# PF11_DigiPot_Cutoff.net
KiCad netlist of a schematic drawn in Altium Designer
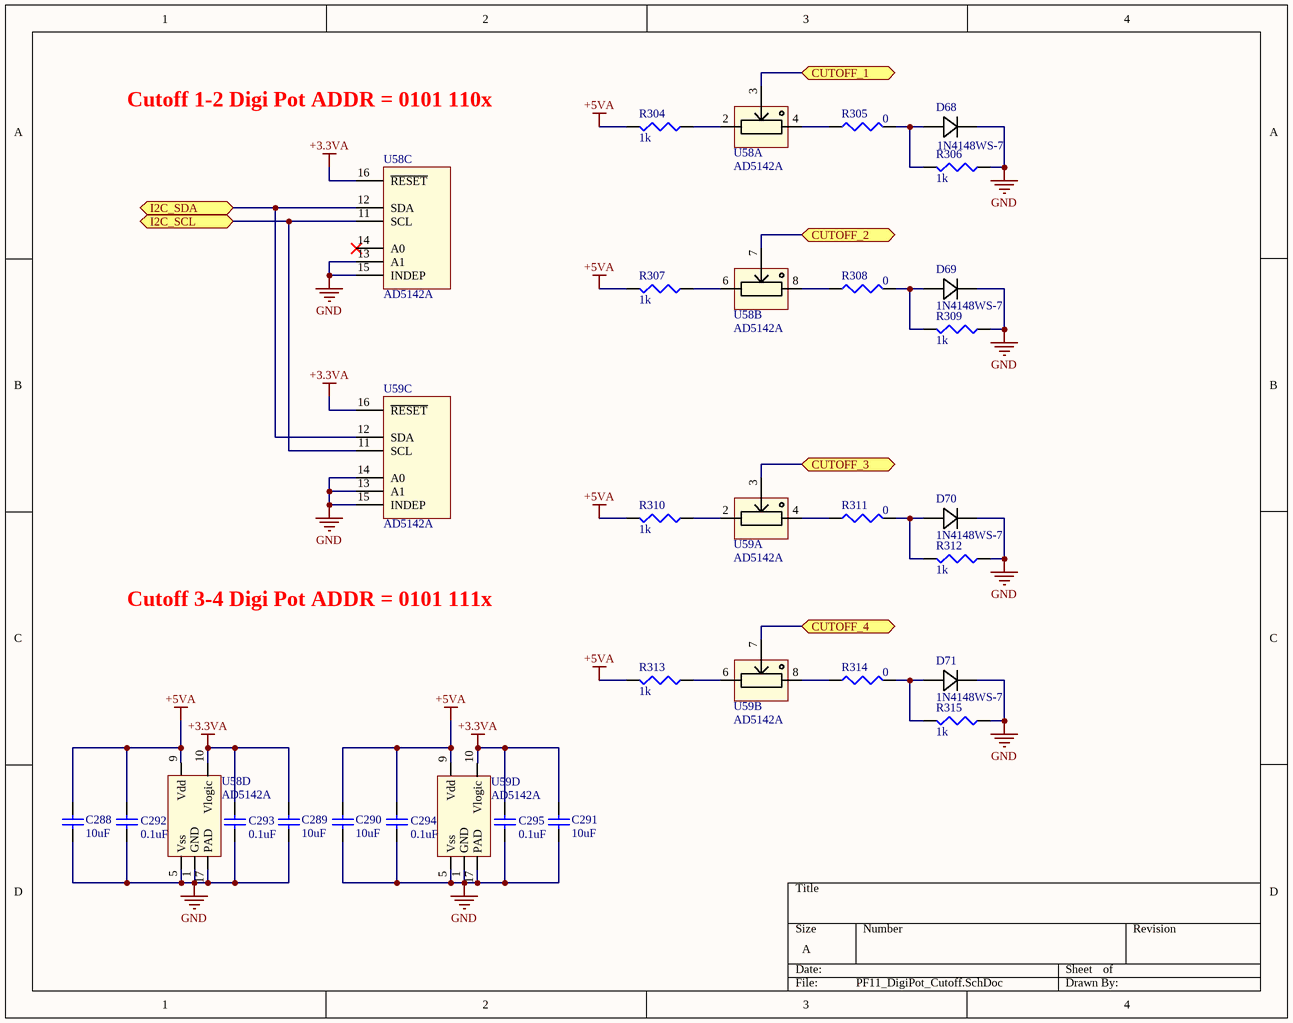
[diagram p0: PF11_DigiPot_Cutoff.SchDoc]

(export (version "E")
  (design (tool "Eeschema 10.0.6"))
  (components
    (comp (ref "C288")
      (value "10uF")
      (footprint "CAPC1608X08")
      (description "Capacitor (Semiconductor SIM Model)")
      (libsource (lib "Michel") (part "Cap Semi"))
    )
    (comp (ref "C289")
      (value "10uF")
      (footprint "CAPC1608X08")
      (description "Capacitor (Semiconductor SIM Model)")
      (libsource (lib "Michel") (part "Cap Semi"))
    )
    (comp (ref "C290")
      (value "10uF")
      (footprint "CAPC1608X08")
      (description "Capacitor (Semiconductor SIM Model)")
      (libsource (lib "Michel") (part "Cap Semi"))
    )
    (comp (ref "C291")
      (value "10uF")
      (footprint "CAPC1608X08")
      (description "Capacitor (Semiconductor SIM Model)")
      (libsource (lib "Michel") (part "Cap Semi"))
    )
    (comp (ref "C292")
      (value "0.1uF")
      (footprint "CAPC1608X08")
      (description "Capacitor (Semiconductor SIM Model)")
      (libsource (lib "Michel") (part "Cap Semi"))
    )
    (comp (ref "C293")
      (value "0.1uF")
      (footprint "CAPC1608X08")
      (description "Capacitor (Semiconductor SIM Model)")
      (libsource (lib "Michel") (part "Cap Semi"))
    )
    (comp (ref "C294")
      (value "0.1uF")
      (footprint "CAPC1608X08")
      (description "Capacitor (Semiconductor SIM Model)")
      (libsource (lib "Michel") (part "Cap Semi"))
    )
    (comp (ref "C295")
      (value "0.1uF")
      (footprint "CAPC1608X08")
      (description "Capacitor (Semiconductor SIM Model)")
      (libsource (lib "Michel") (part "Cap Semi"))
    )
    (comp (ref "D68")
      (value "1N4148WS-7")
      (footprint "SOD323-M")
      (description "Diode signaux faibles")
      (libsource (lib "Michel") (part "1N4148WS-7"))
    )
    (comp (ref "D69")
      (value "1N4148WS-7")
      (footprint "SOD323-M")
      (description "Diode signaux faibles")
      (libsource (lib "Michel") (part "1N4148WS-7"))
    )
    (comp (ref "D70")
      (value "1N4148WS-7")
      (footprint "SOD323-M")
      (description "Diode signaux faibles")
      (libsource (lib "Michel") (part "1N4148WS-7"))
    )
    (comp (ref "D71")
      (value "1N4148WS-7")
      (footprint "SOD323-M")
      (description "Diode signaux faibles")
      (libsource (lib "Michel") (part "1N4148WS-7"))
    )
    (comp (ref "R304")
      (value "1k")
      (footprint "RESC1608X05")
      (description "Resistor")
      (libsource (lib "Michel") (part "Res3"))
    )
    (comp (ref "R305")
      (value "0")
      (footprint "RESC1608X05")
      (description "Resistor")
      (fields (field (name "Comment") "Res3"))
      (libsource (lib "Michel") (part "Res3"))
    )
    (comp (ref "R306")
      (value "1k")
      (footprint "RESC1608X05")
      (description "Resistor")
      (libsource (lib "Michel") (part "Res3"))
    )
    (comp (ref "R307")
      (value "1k")
      (footprint "RESC1608X05")
      (description "Resistor")
      (libsource (lib "Michel") (part "Res3"))
    )
    (comp (ref "R308")
      (value "0")
      (footprint "RESC1608X05")
      (description "Resistor")
      (fields (field (name "Comment") "Res3"))
      (libsource (lib "Michel") (part "Res3"))
    )
    (comp (ref "R309")
      (value "1k")
      (footprint "RESC1608X05")
      (description "Resistor")
      (libsource (lib "Michel") (part "Res3"))
    )
    (comp (ref "R310")
      (value "1k")
      (footprint "RESC1608X05")
      (description "Resistor")
      (libsource (lib "Michel") (part "Res3"))
    )
    (comp (ref "R311")
      (value "0")
      (footprint "RESC1608X05")
      (description "Resistor")
      (fields (field (name "Comment") "Res3"))
      (libsource (lib "Michel") (part "Res3"))
    )
    (comp (ref "R312")
      (value "1k")
      (footprint "RESC1608X05")
      (description "Resistor")
      (libsource (lib "Michel") (part "Res3"))
    )
    (comp (ref "R313")
      (value "1k")
      (footprint "RESC1608X05")
      (description "Resistor")
      (libsource (lib "Michel") (part "Res3"))
    )
    (comp (ref "R314")
      (value "0")
      (footprint "RESC1608X05")
      (description "Resistor")
      (fields (field (name "Comment") "Res3"))
      (libsource (lib "Michel") (part "Res3"))
    )
    (comp (ref "R315")
      (value "1k")
      (footprint "RESC1608X05")
      (description "Resistor")
      (libsource (lib "Michel") (part "Res3"))
    )
    (comp (ref "U58")
      (value "AD5142A")
      (footprint "LFCSP16_AD5142")
      (description "Dual DigiPot non volatile 10Klog I2C")
      (libsource (lib "") (part "AD5142A_1"))
    )
    (comp (ref "U59")
      (value "AD5142A")
      (footprint "LFCSP16_AD5142")
      (description "Dual DigiPot non volatile 10Klog I2C")
      (libsource (lib "Michel") (part "AD5142A"))
    )
  )
  (nets
    (net (code "1") (name "+3.3VA") (class "Default")
      (node (ref "C289") (pin "1") (pinfunction "1_1") (pintype "passive"))
      (node (ref "C291") (pin "1") (pinfunction "1_1") (pintype "passive"))
      (node (ref "C293") (pin "1") (pinfunction "1_1") (pintype "passive"))
      (node (ref "C295") (pin "1") (pinfunction "1_1") (pintype "passive"))
      (node (ref "U58") (pin "10") (pinfunction "Vlogic_10") (pintype "power_in"))
      (node (ref "U58") (pin "16") (pinfunction "~{RESET}_16") (pintype "passive"))
      (node (ref "U59") (pin "10") (pinfunction "Vlogic_10") (pintype "power_in"))
      (node (ref "U59") (pin "16") (pinfunction "~{RESET}_16") (pintype "passive"))
    )
    (net (code "2") (name "+5VA") (class "Default")
      (node (ref "C288") (pin "1") (pinfunction "1_1") (pintype "passive"))
      (node (ref "C290") (pin "1") (pinfunction "1_1") (pintype "passive"))
      (node (ref "C292") (pin "1") (pinfunction "1_1") (pintype "passive"))
      (node (ref "C294") (pin "1") (pinfunction "1_1") (pintype "passive"))
      (node (ref "R304") (pin "2") (pinfunction "2_2") (pintype "passive"))
      (node (ref "R307") (pin "2") (pinfunction "2_2") (pintype "passive"))
      (node (ref "R310") (pin "2") (pinfunction "2_2") (pintype "passive"))
      (node (ref "R313") (pin "2") (pinfunction "2_2") (pintype "passive"))
      (node (ref "U58") (pin "9") (pinfunction "Vdd_9") (pintype "power_in"))
      (node (ref "U59") (pin "9") (pinfunction "Vdd_9") (pintype "power_in"))
    )
    (net (code "3") (name "/CUTOFF_1") (class "Default")
      (node (ref "U58") (pin "3") (pinfunction "P0W_3") (pintype "passive"))
    )
    (net (code "4") (name "/CUTOFF_2") (class "Default")
      (node (ref "U58") (pin "7") (pinfunction "P1W_7") (pintype "passive"))
    )
    (net (code "5") (name "/CUTOFF_3") (class "Default")
      (node (ref "U59") (pin "3") (pinfunction "P0W_3") (pintype "passive"))
    )
    (net (code "6") (name "/CUTOFF_4") (class "Default")
      (node (ref "U59") (pin "7") (pinfunction "P1W_7") (pintype "passive"))
    )
    (net (code "7") (name "/I2C_SCL") (class "Default")
      (node (ref "U58") (pin "11") (pinfunction "SCL_11") (pintype "passive"))
      (node (ref "U59") (pin "11") (pinfunction "SCL_11") (pintype "passive"))
    )
    (net (code "8") (name "/I2C_SDA") (class "Default")
      (node (ref "U58") (pin "12") (pinfunction "SDA_12") (pintype "passive"))
      (node (ref "U59") (pin "12") (pinfunction "SDA_12") (pintype "passive"))
    )
    (net (code "9") (name "GND") (class "Default")
      (node (ref "C288") (pin "2") (pinfunction "2_2") (pintype "passive"))
      (node (ref "C289") (pin "2") (pinfunction "2_2") (pintype "passive"))
      (node (ref "C290") (pin "2") (pinfunction "2_2") (pintype "passive"))
      (node (ref "C291") (pin "2") (pinfunction "2_2") (pintype "passive"))
      (node (ref "C292") (pin "2") (pinfunction "2_2") (pintype "passive"))
      (node (ref "C293") (pin "2") (pinfunction "2_2") (pintype "passive"))
      (node (ref "C294") (pin "2") (pinfunction "2_2") (pintype "passive"))
      (node (ref "C295") (pin "2") (pinfunction "2_2") (pintype "passive"))
      (node (ref "D68") (pin "1") (pinfunction "1_1") (pintype "passive"))
      (node (ref "D69") (pin "1") (pinfunction "1_1") (pintype "passive"))
      (node (ref "D70") (pin "1") (pinfunction "1_1") (pintype "passive"))
      (node (ref "D71") (pin "1") (pinfunction "1_1") (pintype "passive"))
      (node (ref "R306") (pin "1") (pinfunction "1_1") (pintype "passive"))
      (node (ref "R309") (pin "1") (pinfunction "1_1") (pintype "passive"))
      (node (ref "R312") (pin "1") (pinfunction "1_1") (pintype "passive"))
      (node (ref "R315") (pin "1") (pinfunction "1_1") (pintype "passive"))
      (node (ref "U58") (pin "1") (pinfunction "GND_1") (pintype "power_in"))
      (node (ref "U58") (pin "13") (pinfunction "A1_13") (pintype "power_in"))
      (node (ref "U58") (pin "15") (pinfunction "INDEP_15") (pintype "power_in"))
      (node (ref "U58") (pin "17") (pinfunction "PAD_17") (pintype "power_in"))
      (node (ref "U58") (pin "5") (pinfunction "Vss_5") (pintype "power_in"))
      (node (ref "U59") (pin "1") (pinfunction "GND_1") (pintype "power_in"))
      (node (ref "U59") (pin "13") (pinfunction "A1_13") (pintype "power_in"))
      (node (ref "U59") (pin "14") (pinfunction "A0_14") (pintype "power_in"))
      (node (ref "U59") (pin "15") (pinfunction "INDEP_15") (pintype "power_in"))
      (node (ref "U59") (pin "17") (pinfunction "PAD_17") (pintype "power_in"))
      (node (ref "U59") (pin "5") (pinfunction "Vss_5") (pintype "power_in"))
    )
    (net (code "10") (name "Net-(D68-Pad2)") (class "Default")
      (node (ref "D68") (pin "2") (pinfunction "2_2") (pintype "passive"))
      (node (ref "R305") (pin "2") (pinfunction "2_2") (pintype "passive"))
      (node (ref "R306") (pin "2") (pinfunction "2_2") (pintype "passive"))
    )
    (net (code "11") (name "Net-(D69-Pad2)") (class "Default")
      (node (ref "D69") (pin "2") (pinfunction "2_2") (pintype "passive"))
      (node (ref "R308") (pin "2") (pinfunction "2_2") (pintype "passive"))
      (node (ref "R309") (pin "2") (pinfunction "2_2") (pintype "passive"))
    )
    (net (code "12") (name "Net-(D70-Pad2)") (class "Default")
      (node (ref "D70") (pin "2") (pinfunction "2_2") (pintype "passive"))
      (node (ref "R311") (pin "2") (pinfunction "2_2") (pintype "passive"))
      (node (ref "R312") (pin "2") (pinfunction "2_2") (pintype "passive"))
    )
    (net (code "13") (name "Net-(D71-Pad2)") (class "Default")
      (node (ref "D71") (pin "2") (pinfunction "2_2") (pintype "passive"))
      (node (ref "R314") (pin "2") (pinfunction "2_2") (pintype "passive"))
      (node (ref "R315") (pin "2") (pinfunction "2_2") (pintype "passive"))
    )
    (net (code "14") (name "Net-(U58A-P0A)") (class "Default")
      (node (ref "R304") (pin "1") (pinfunction "1_1") (pintype "passive"))
      (node (ref "U58") (pin "2") (pinfunction "P0A_2") (pintype "passive"))
    )
    (net (code "15") (name "Net-(U58A-P0B)") (class "Default")
      (node (ref "R305") (pin "1") (pinfunction "1_1") (pintype "passive"))
      (node (ref "U58") (pin "4") (pinfunction "P0B_4") (pintype "passive"))
    )
    (net (code "16") (name "Net-(U58B-P1A)") (class "Default")
      (node (ref "R307") (pin "1") (pinfunction "1_1") (pintype "passive"))
      (node (ref "U58") (pin "6") (pinfunction "P1A_6") (pintype "passive"))
    )
    (net (code "17") (name "Net-(U58B-P1B)") (class "Default")
      (node (ref "R308") (pin "1") (pinfunction "1_1") (pintype "passive"))
      (node (ref "U58") (pin "8") (pinfunction "P1B_8") (pintype "passive"))
    )
    (net (code "18") (name "Net-(U59A-P0A)") (class "Default")
      (node (ref "R310") (pin "1") (pinfunction "1_1") (pintype "passive"))
      (node (ref "U59") (pin "2") (pinfunction "P0A_2") (pintype "passive"))
    )
    (net (code "19") (name "Net-(U59A-P0B)") (class "Default")
      (node (ref "R311") (pin "1") (pinfunction "1_1") (pintype "passive"))
      (node (ref "U59") (pin "4") (pinfunction "P0B_4") (pintype "passive"))
    )
    (net (code "20") (name "Net-(U59B-P1A)") (class "Default")
      (node (ref "R313") (pin "1") (pinfunction "1_1") (pintype "passive"))
      (node (ref "U59") (pin "6") (pinfunction "P1A_6") (pintype "passive"))
    )
    (net (code "21") (name "Net-(U59B-P1B)") (class "Default")
      (node (ref "R314") (pin "1") (pinfunction "1_1") (pintype "passive"))
      (node (ref "U59") (pin "8") (pinfunction "P1B_8") (pintype "passive"))
    )
    (net (code "22") (name "unconnected-(U58C-A0-Pad14)") (class "Default")
      (node (ref "U58") (pin "14") (pinfunction "A0_14") (pintype "power_in+no_connect"))
    )
  )
)
